# HMC480.net
KiCad netlist of a schematic drawn in Altium Designer
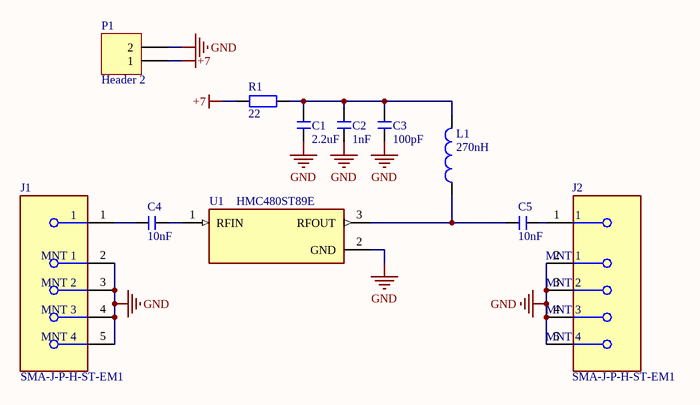
[diagram p0: HMC480.SchDoc]

(export (version "E")
  (design (tool "Eeschema 10.0.6"))
  (components
    (comp (ref "C1")
      (value "2.2uF")
      (footprint "C 0603_L")
      (description "贴片电容")
      (libsource (lib "01 - 电容-电阻-电感") (part "C"))
    )
    (comp (ref "C2")
      (value "1nF")
      (footprint "C 0603_L")
      (description "贴片电容")
      (libsource (lib "01 - 电容-电阻-电感") (part "C"))
    )
    (comp (ref "C3")
      (value "100pF")
      (footprint "C 0603_L")
      (description "贴片电容")
      (libsource (lib "01 - 电容-电阻-电感") (part "C"))
    )
    (comp (ref "C4")
      (value "10nF")
      (footprint "C 0603_L")
      (description "贴片电容")
      (libsource (lib "01 - 电容-电阻-电感") (part "C"))
    )
    (comp (ref "C5")
      (value "10nF")
      (footprint "C 0603_L")
      (description "贴片电容")
      (libsource (lib "01 - 电容-电阻-电感") (part "C"))
    )
    (comp (ref "J1")
      (value "SMA-J-P-H-ST-EM1")
      (footprint "FP-SMA-J-P-H-ST-EM1-MFG")
      (description "CONN SMA JACK STR 50OHM EDGE MNT")
      (libsource (lib "") (part "c65b8a639cdaef1819ea20b5466f8fa_1"))
    )
    (comp (ref "J2")
      (value "SMA-J-P-H-ST-EM1")
      (footprint "FP-SMA-J-P-H-ST-EM1-MFG")
      (description "CONN SMA JACK STR 50OHM EDGE MNT")
      (libsource (lib "Altium Content Vault") (part "c65b8a639cdaef1819ea20b5466f8fa"))
    )
    (comp (ref "L1")
      (value "270nH")
      (footprint "L 0805")
      (description "小功率贴片电感")
      (libsource (lib "01 - 电容-电阻-电感") (part "L"))
    )
    (comp (ref "P1")
      (value "Header 2")
      (footprint "HDR1X2")
      (description "Header, 2-Pin")
      (fields (field (name "PUBLISHER") "Altium Limited"))
      (libsource (lib "Miscellaneous Connectors") (part "Header 2"))
    )
    (comp (ref "R1")
      (value "22")
      (footprint "R 1812_M")
      (description "贴片电阻")
      (libsource (lib "01 - 电容-电阻-电感") (part "R"))
    )
    (comp (ref "U1")
      (value "HMC480ST89E")
      (footprint "FP-RK-3-MFG")
      (description "IC RF AMP GP 0HZ-5GHZ SOT89")
      (libsource (lib "Altium Content Vault") (part "049cc02af2bdf6ac426b0910cff47dc"))
    )
  )
  (nets
    (net (code "1") (name "+7") (class "Default")
      (node (ref "P1") (pin "1") (pinfunction "1_1") (pintype "passive"))
      (node (ref "R1") (pin "1") (pinfunction "1_1") (pintype "passive"))
    )
    (net (code "2") (name "GND") (class "Default")
      (node (ref "C1") (pin "1") (pinfunction "1_1") (pintype "passive"))
      (node (ref "C2") (pin "1") (pinfunction "1_1") (pintype "passive"))
      (node (ref "C3") (pin "1") (pinfunction "1_1") (pintype "passive"))
      (node (ref "J1") (pin "2") (pinfunction "MNT_1_2") (pintype "passive"))
      (node (ref "J1") (pin "3") (pinfunction "MNT_2_3") (pintype "passive"))
      (node (ref "J1") (pin "4") (pinfunction "MNT_3_4") (pintype "passive"))
      (node (ref "J1") (pin "5") (pinfunction "MNT_4_5") (pintype "passive"))
      (node (ref "J2") (pin "2") (pinfunction "MNT_1_2") (pintype "passive"))
      (node (ref "J2") (pin "3") (pinfunction "MNT_2_3") (pintype "passive"))
      (node (ref "J2") (pin "4") (pinfunction "MNT_3_4") (pintype "passive"))
      (node (ref "J2") (pin "5") (pinfunction "MNT_4_5") (pintype "passive"))
      (node (ref "P1") (pin "2") (pinfunction "2_2") (pintype "passive"))
      (node (ref "U1") (pin "2") (pinfunction "GND_2") (pintype "power_in"))
    )
    (net (code "3") (name "Net-(C1-Pad2)") (class "Default")
      (node (ref "C1") (pin "2") (pinfunction "2_2") (pintype "passive"))
      (node (ref "C2") (pin "2") (pinfunction "2_2") (pintype "passive"))
      (node (ref "C3") (pin "2") (pinfunction "2_2") (pintype "passive"))
      (node (ref "L1") (pin "2") (pinfunction "2_2") (pintype "passive"))
      (node (ref "R1") (pin "2") (pinfunction "2_2") (pintype "passive"))
    )
    (net (code "4") (name "Net-(C4-Pad1)") (class "Default")
      (node (ref "C4") (pin "1") (pinfunction "1_1") (pintype "passive"))
      (node (ref "J1") (pin "1") (pinfunction "1_1") (pintype "passive"))
    )
    (net (code "5") (name "Net-(C5-Pad2)") (class "Default")
      (node (ref "C5") (pin "2") (pinfunction "2_2") (pintype "passive"))
      (node (ref "J2") (pin "1") (pinfunction "1_1") (pintype "passive"))
    )
    (net (code "6") (name "Net-(U1-RFIN)") (class "Default")
      (node (ref "C4") (pin "2") (pinfunction "2_2") (pintype "passive"))
      (node (ref "U1") (pin "1") (pinfunction "RFIN_1") (pintype "input"))
    )
    (net (code "7") (name "Net-(U1-RFOUT)") (class "Default")
      (node (ref "C5") (pin "1") (pinfunction "1_1") (pintype "passive"))
      (node (ref "L1") (pin "1") (pinfunction "1_1") (pintype "passive"))
      (node (ref "U1") (pin "3") (pinfunction "RFOUT_3") (pintype "output"))
    )
  )
)
